# Display_driver.net
KiCad netlist of a schematic drawn in Altium Designer
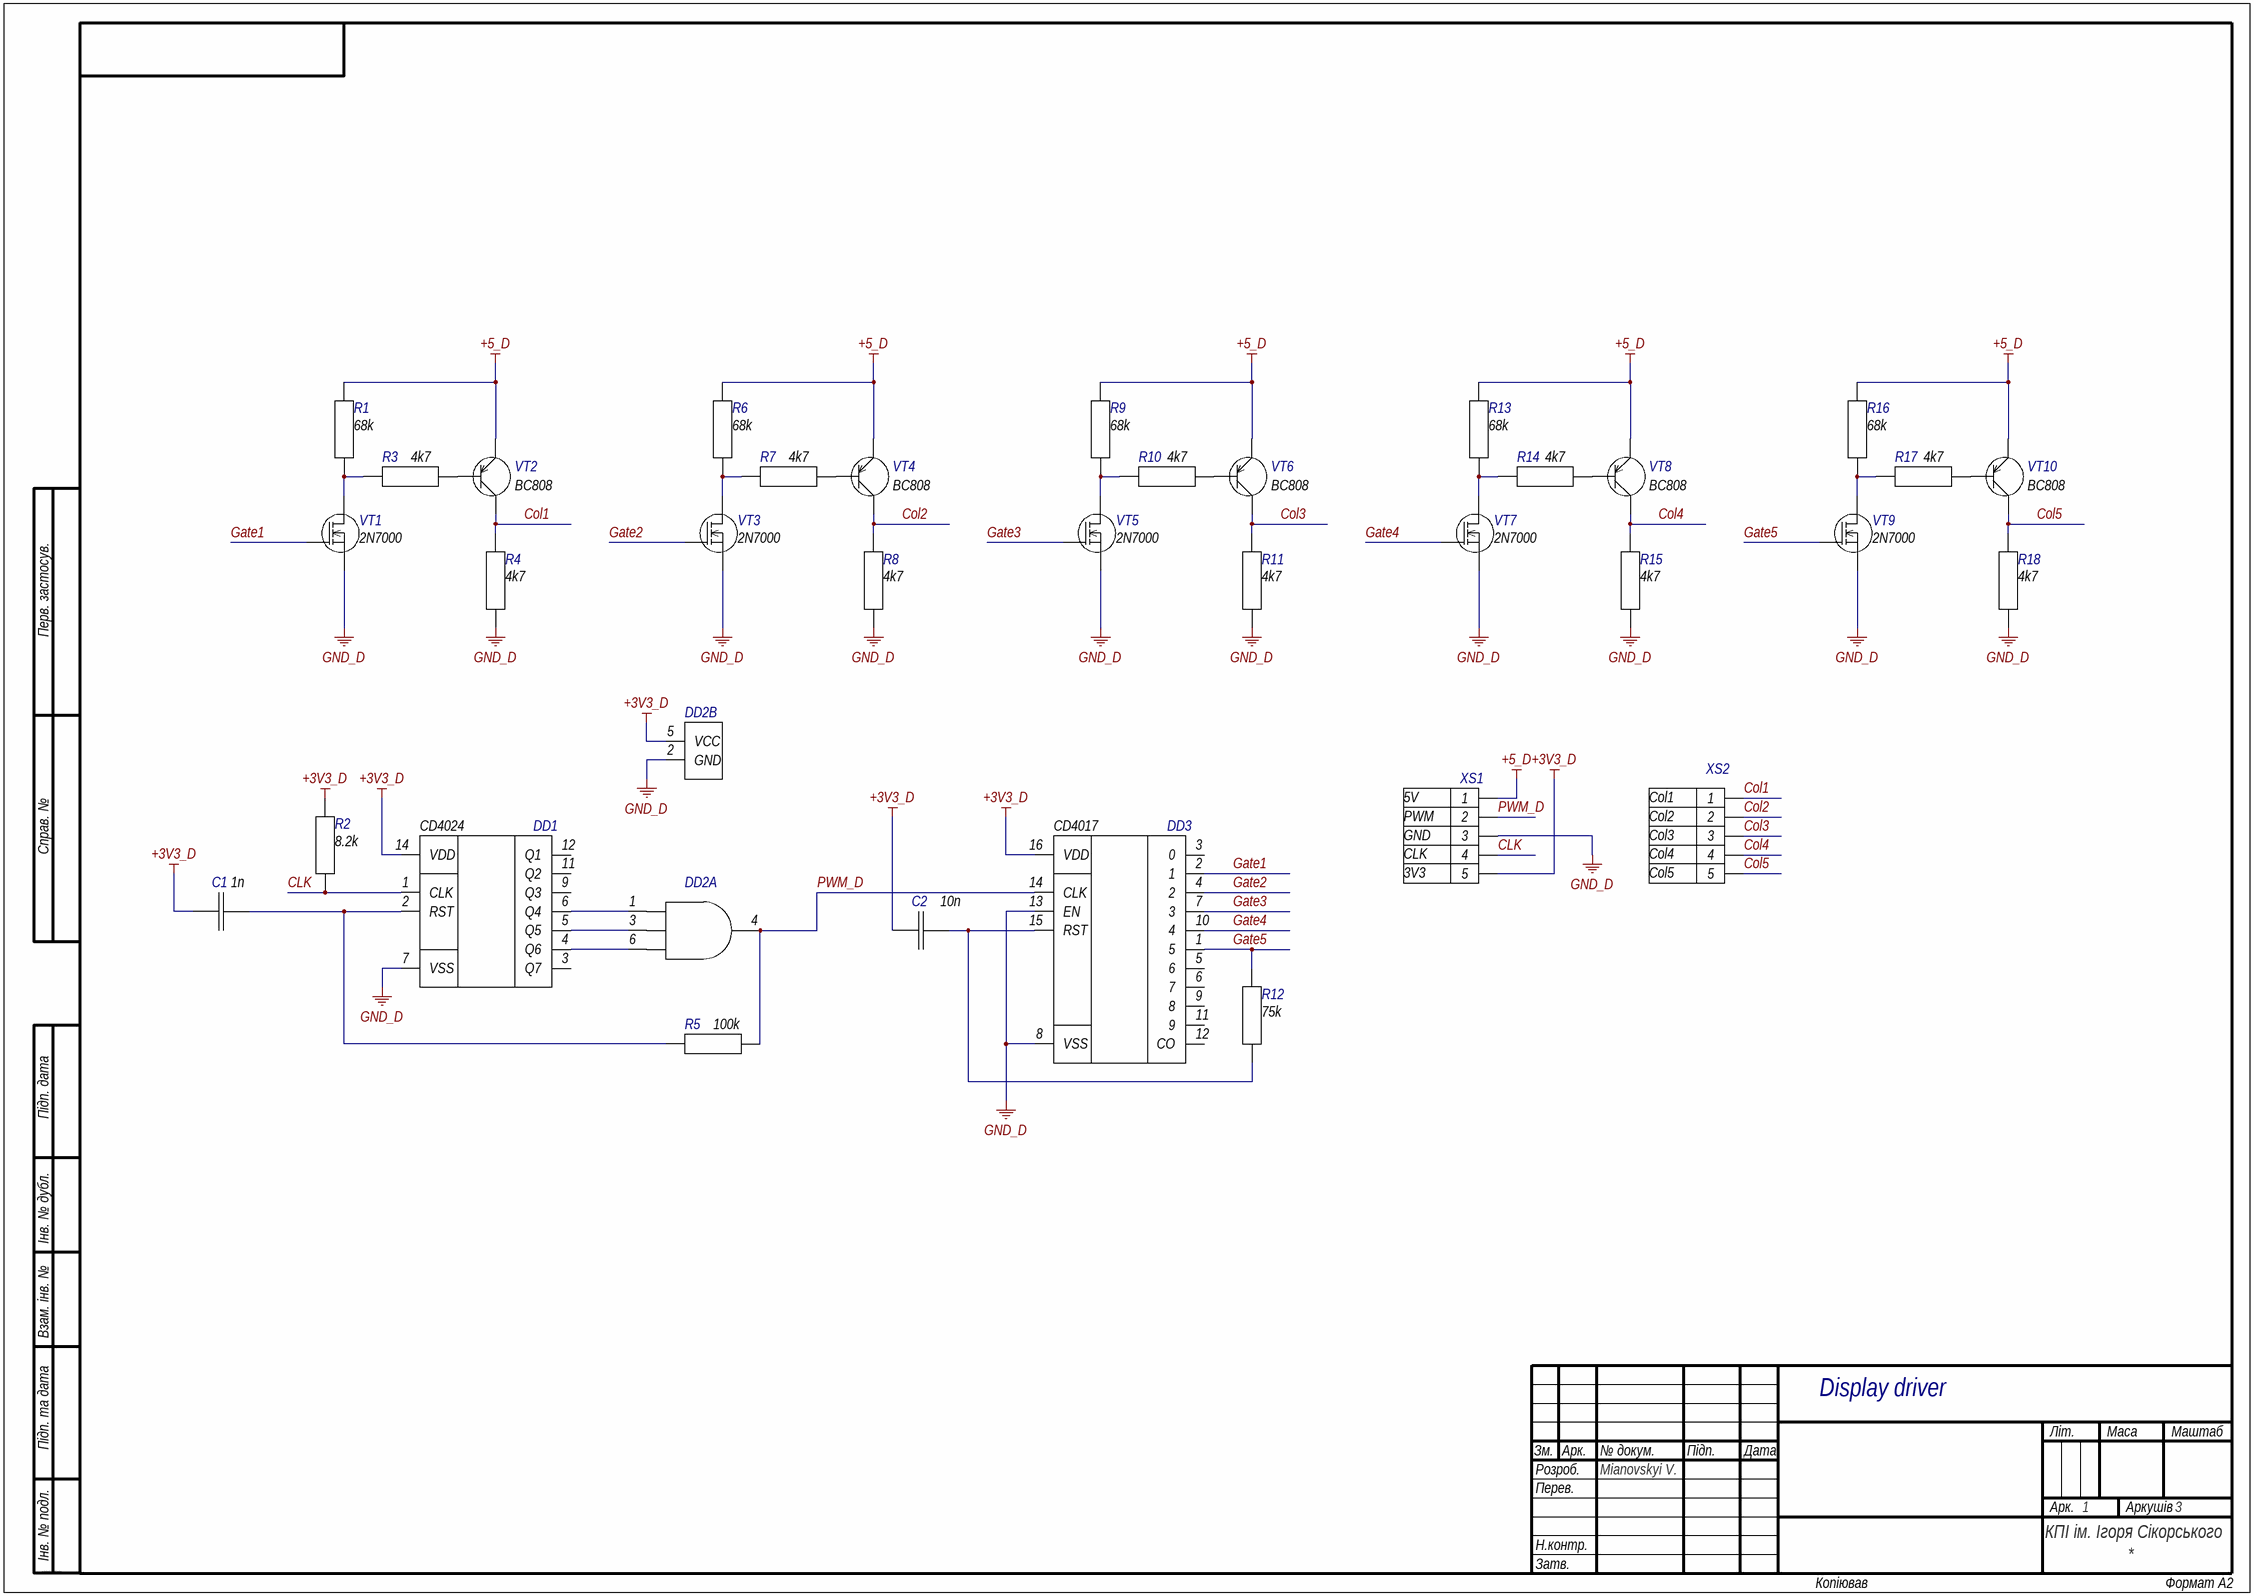
[diagram p0: Display_driver.SchDoc]

(export (version "E")
  (design (tool "Eeschema 10.0.6"))
  (components
    (comp (ref "C1")
      (value "1n")
      (footprint "CHIP-0805")
      (fields (field (name "Comment") "C0805"))
      (libsource (lib "Schlib1") (part "C0805"))
    )
    (comp (ref "C2")
      (value "10n")
      (footprint "CHIP-0402")
      (fields (field (name "Comment") "C0805"))
      (libsource (lib "Schlib1") (part "C0805"))
    )
    (comp (ref "DD1")
      (value "CD4024")
      (footprint "SOIC-14")
      (fields (field (name "NAME") "CD4024"))
      (libsource (lib "Schlib1") (part "CD4024"))
    )
    (comp (ref "DD2")
      (value "74LVC1G11")
      (footprint "SOT23-6")
      (libsource (lib "Schlib1") (part "74LVC1G11"))
    )
    (comp (ref "DD3")
      (value "CD4017")
      (footprint "SOIC-16")
      (fields (field (name "NAME") "CD4017"))
      (libsource (lib "Schlib1") (part "CD4017"))
    )
    (comp (ref "R1")
      (value "68k")
      (footprint "CHIP-0805")
      (fields (field (name "Comment") "R0805"))
      (libsource (lib "Schlib1") (part "R0805"))
    )
    (comp (ref "R2")
      (value "8.2k")
      (footprint "CHIP-0805")
      (fields (field (name "Comment") "R0805"))
      (libsource (lib "Schlib1") (part "R0805"))
    )
    (comp (ref "R3")
      (value "4k7")
      (footprint "CHIP-0402")
      (fields (field (name "Comment") "R0805"))
      (libsource (lib "") (part "R0805_1"))
    )
    (comp (ref "R4")
      (value "4k7")
      (footprint "CHIP-0402")
      (fields (field (name "Comment") "R0805"))
      (libsource (lib "Schlib1") (part "R0805"))
    )
    (comp (ref "R5")
      (value "100k")
      (footprint "CHIP-0805")
      (fields (field (name "Comment") "R0805"))
      (libsource (lib "") (part "R0805_1"))
    )
    (comp (ref "R6")
      (value "68k")
      (footprint "CHIP-0805")
      (fields (field (name "Comment") "R0805"))
      (libsource (lib "Schlib1") (part "R0805"))
    )
    (comp (ref "R7")
      (value "4k7")
      (footprint "CHIP-0402")
      (fields (field (name "Comment") "R0805"))
      (libsource (lib "") (part "R0805_1"))
    )
    (comp (ref "R8")
      (value "4k7")
      (footprint "CHIP-0402")
      (fields (field (name "Comment") "R0805"))
      (libsource (lib "Schlib1") (part "R0805"))
    )
    (comp (ref "R9")
      (value "68k")
      (footprint "CHIP-0805")
      (fields (field (name "Comment") "R0805"))
      (libsource (lib "Schlib1") (part "R0805"))
    )
    (comp (ref "R10")
      (value "4k7")
      (footprint "CHIP-0402")
      (fields (field (name "Comment") "R0805"))
      (libsource (lib "") (part "R0805_1"))
    )
    (comp (ref "R11")
      (value "4k7")
      (footprint "CHIP-0402")
      (fields (field (name "Comment") "R0805"))
      (libsource (lib "Schlib1") (part "R0805"))
    )
    (comp (ref "R12")
      (value "75k")
      (footprint "CHIP-0402")
      (fields (field (name "Comment") "R0805"))
      (libsource (lib "Schlib1") (part "R0805"))
    )
    (comp (ref "R13")
      (value "68k")
      (footprint "CHIP-0805")
      (fields (field (name "Comment") "R0805"))
      (libsource (lib "Schlib1") (part "R0805"))
    )
    (comp (ref "R14")
      (value "4k7")
      (footprint "CHIP-0402")
      (fields (field (name "Comment") "R0805"))
      (libsource (lib "") (part "R0805_1"))
    )
    (comp (ref "R15")
      (value "4k7")
      (footprint "CHIP-0402")
      (fields (field (name "Comment") "R0805"))
      (libsource (lib "Schlib1") (part "R0805"))
    )
    (comp (ref "R16")
      (value "68k")
      (footprint "CHIP-0805")
      (fields (field (name "Comment") "R0805"))
      (libsource (lib "Schlib1") (part "R0805"))
    )
    (comp (ref "R17")
      (value "4k7")
      (footprint "CHIP-0402")
      (fields (field (name "Comment") "R0805"))
      (libsource (lib "") (part "R0805_1"))
    )
    (comp (ref "R18")
      (value "4k7")
      (footprint "CHIP-0402")
      (fields (field (name "Comment") "R0805"))
      (libsource (lib "Schlib1") (part "R0805"))
    )
    (comp (ref "VT1")
      (value "2N7000")
      (footprint "SOT23-3")
      (fields (field (name "NAME") "2N7000"))
      (libsource (lib "Schlib1") (part "2N7000"))
    )
    (comp (ref "VT2")
      (value "BC808")
      (footprint "SOT23-3")
      (fields (field (name "NAME") "BC808"))
      (libsource (lib "Schlib1") (part "BC808"))
    )
    (comp (ref "VT3")
      (value "2N7000")
      (footprint "SOT23-3")
      (fields (field (name "NAME") "2N7000"))
      (libsource (lib "Schlib1") (part "2N7000"))
    )
    (comp (ref "VT4")
      (value "BC808")
      (footprint "SOT23-3")
      (fields (field (name "NAME") "BC808"))
      (libsource (lib "Schlib1") (part "BC808"))
    )
    (comp (ref "VT5")
      (value "2N7000")
      (footprint "SOT23-3")
      (fields (field (name "NAME") "2N7000"))
      (libsource (lib "Schlib1") (part "2N7000"))
    )
    (comp (ref "VT6")
      (value "BC808")
      (footprint "SOT23-3")
      (fields (field (name "NAME") "BC808"))
      (libsource (lib "Schlib1") (part "BC808"))
    )
    (comp (ref "VT7")
      (value "2N7000")
      (footprint "SOT23-3")
      (fields (field (name "NAME") "2N7000"))
      (libsource (lib "Schlib1") (part "2N7000"))
    )
    (comp (ref "VT8")
      (value "BC808")
      (footprint "SOT23-3")
      (fields (field (name "NAME") "BC808"))
      (libsource (lib "Schlib1") (part "BC808"))
    )
    (comp (ref "VT9")
      (value "2N7000")
      (footprint "SOT23-3")
      (fields (field (name "NAME") "2N7000"))
      (libsource (lib "Schlib1") (part "2N7000"))
    )
    (comp (ref "VT10")
      (value "BC808")
      (footprint "SOT23-3")
      (fields (field (name "NAME") "BC808"))
      (libsource (lib "Schlib1") (part "BC808"))
    )
    (comp (ref "XS1")
      (value "Socket")
      (footprint "SOCKET")
      (fields
        (field (name "PIN5") "3V3")
        (field (name "PIN4") "CLK")
        (field (name "PIN3") "GND")
        (field (name "PIN2") "PWM")
        (field (name "PIN1") "5V")
      )
      (libsource (lib "Schlib1") (part "Socket"))
    )
    (comp (ref "XS2")
      (value "Socket")
      (footprint "SOCKET")
      (fields
        (field (name "PIN5") "Col5")
        (field (name "PIN4") "Col4")
        (field (name "PIN3") "Col3")
        (field (name "PIN2") "Col2")
        (field (name "PIN1") "Col1")
      )
      (libsource (lib "Schlib1") (part "Socket"))
    )
  )
  (nets
    (net (code "1") (name "+3V3_D") (class "Default")
      (node (ref "C1") (pin "1") (pinfunction "1_1") (pintype "passive"))
      (node (ref "C2") (pin "1") (pinfunction "1_1") (pintype "passive"))
      (node (ref "DD1") (pin "14") (pinfunction "VDD_14") (pintype "passive"))
      (node (ref "DD2") (pin "5") (pinfunction "VCC_5") (pintype "passive"))
      (node (ref "DD3") (pin "16") (pinfunction "VDD_16") (pintype "passive"))
      (node (ref "R2") (pin "2") (pinfunction "2_2") (pintype "passive"))
      (node (ref "XS1") (pin "5") (pinfunction "5_5") (pintype "passive"))
    )
    (net (code "2") (name "+5_D") (class "Default")
      (node (ref "R1") (pin "2") (pinfunction "2_2") (pintype "passive"))
      (node (ref "R13") (pin "2") (pinfunction "2_2") (pintype "passive"))
      (node (ref "R16") (pin "2") (pinfunction "2_2") (pintype "passive"))
      (node (ref "R6") (pin "2") (pinfunction "2_2") (pintype "passive"))
      (node (ref "R9") (pin "2") (pinfunction "2_2") (pintype "passive"))
      (node (ref "VT10") (pin "2") (pinfunction "E_2") (pintype "passive"))
      (node (ref "VT2") (pin "2") (pinfunction "E_2") (pintype "passive"))
      (node (ref "VT4") (pin "2") (pinfunction "E_2") (pintype "passive"))
      (node (ref "VT6") (pin "2") (pinfunction "E_2") (pintype "passive"))
      (node (ref "VT8") (pin "2") (pinfunction "E_2") (pintype "passive"))
      (node (ref "XS1") (pin "1") (pinfunction "1_1") (pintype "passive"))
    )
    (net (code "3") (name "/CLK") (class "Default")
      (node (ref "DD1") (pin "1") (pinfunction "CLK_1") (pintype "passive"))
      (node (ref "R2") (pin "1") (pinfunction "1_1") (pintype "passive"))
      (node (ref "XS1") (pin "4") (pinfunction "4_4") (pintype "passive"))
    )
    (net (code "4") (name "/Col1") (class "Default")
      (node (ref "R4") (pin "2") (pinfunction "2_2") (pintype "passive"))
      (node (ref "VT2") (pin "3") (pinfunction "C_3") (pintype "passive"))
      (node (ref "XS2") (pin "1") (pinfunction "1_1") (pintype "passive"))
    )
    (net (code "5") (name "/Col2") (class "Default")
      (node (ref "R8") (pin "2") (pinfunction "2_2") (pintype "passive"))
      (node (ref "VT4") (pin "3") (pinfunction "C_3") (pintype "passive"))
      (node (ref "XS2") (pin "2") (pinfunction "2_2") (pintype "passive"))
    )
    (net (code "6") (name "/Col3") (class "Default")
      (node (ref "R11") (pin "2") (pinfunction "2_2") (pintype "passive"))
      (node (ref "VT6") (pin "3") (pinfunction "C_3") (pintype "passive"))
      (node (ref "XS2") (pin "3") (pinfunction "3_3") (pintype "passive"))
    )
    (net (code "7") (name "/Col4") (class "Default")
      (node (ref "R15") (pin "2") (pinfunction "2_2") (pintype "passive"))
      (node (ref "VT8") (pin "3") (pinfunction "C_3") (pintype "passive"))
      (node (ref "XS2") (pin "4") (pinfunction "4_4") (pintype "passive"))
    )
    (net (code "8") (name "/Col5") (class "Default")
      (node (ref "R18") (pin "2") (pinfunction "2_2") (pintype "passive"))
      (node (ref "VT10") (pin "3") (pinfunction "C_3") (pintype "passive"))
      (node (ref "XS2") (pin "5") (pinfunction "5_5") (pintype "passive"))
    )
    (net (code "9") (name "/Gate1") (class "Default")
      (node (ref "DD3") (pin "2") (pinfunction "1_2") (pintype "passive"))
      (node (ref "VT1") (pin "1") (pinfunction "G_1") (pintype "passive"))
    )
    (net (code "10") (name "/Gate2") (class "Default")
      (node (ref "DD3") (pin "4") (pinfunction "2_4") (pintype "passive"))
      (node (ref "VT3") (pin "1") (pinfunction "G_1") (pintype "passive"))
    )
    (net (code "11") (name "/Gate3") (class "Default")
      (node (ref "DD3") (pin "7") (pinfunction "3_7") (pintype "passive"))
      (node (ref "VT5") (pin "1") (pinfunction "G_1") (pintype "passive"))
    )
    (net (code "12") (name "/Gate4") (class "Default")
      (node (ref "DD3") (pin "10") (pinfunction "4_10") (pintype "passive"))
      (node (ref "VT7") (pin "1") (pinfunction "G_1") (pintype "passive"))
    )
    (net (code "13") (name "/Gate5") (class "Default")
      (node (ref "DD3") (pin "1") (pinfunction "5_1") (pintype "passive"))
      (node (ref "R12") (pin "2") (pinfunction "2_2") (pintype "passive"))
      (node (ref "VT9") (pin "1") (pinfunction "G_1") (pintype "passive"))
    )
    (net (code "14") (name "/PWM_D") (class "Default")
      (node (ref "DD2") (pin "4") (pinfunction "Y_4") (pintype "passive"))
      (node (ref "DD3") (pin "14") (pinfunction "CLK_14") (pintype "passive"))
      (node (ref "R5") (pin "2") (pinfunction "2_2") (pintype "passive"))
      (node (ref "XS1") (pin "2") (pinfunction "2_2") (pintype "passive"))
    )
    (net (code "15") (name "GND_D") (class "Default")
      (node (ref "DD1") (pin "7") (pinfunction "VSS_7") (pintype "passive"))
      (node (ref "DD2") (pin "2") (pinfunction "GND_2") (pintype "passive"))
      (node (ref "DD3") (pin "13") (pinfunction "EN_13") (pintype "passive"))
      (node (ref "DD3") (pin "8") (pinfunction "VSS_8") (pintype "passive"))
      (node (ref "R11") (pin "1") (pinfunction "1_1") (pintype "passive"))
      (node (ref "R15") (pin "1") (pinfunction "1_1") (pintype "passive"))
      (node (ref "R18") (pin "1") (pinfunction "1_1") (pintype "passive"))
      (node (ref "R4") (pin "1") (pinfunction "1_1") (pintype "passive"))
      (node (ref "R8") (pin "1") (pinfunction "1_1") (pintype "passive"))
      (node (ref "VT1") (pin "2") (pinfunction "S_2") (pintype "passive"))
      (node (ref "VT3") (pin "2") (pinfunction "S_2") (pintype "passive"))
      (node (ref "VT5") (pin "2") (pinfunction "S_2") (pintype "passive"))
      (node (ref "VT7") (pin "2") (pinfunction "S_2") (pintype "passive"))
      (node (ref "VT9") (pin "2") (pinfunction "S_2") (pintype "passive"))
      (node (ref "XS1") (pin "3") (pinfunction "3_3") (pintype "passive"))
    )
    (net (code "16") (name "Net-(DD1-Q4)") (class "Default")
      (node (ref "DD1") (pin "6") (pinfunction "Q4_6") (pintype "passive"))
      (node (ref "DD2") (pin "1") (pinfunction "A_1") (pintype "passive"))
    )
    (net (code "17") (name "Net-(DD1-Q5)") (class "Default")
      (node (ref "DD1") (pin "5") (pinfunction "Q5_5") (pintype "passive"))
      (node (ref "DD2") (pin "3") (pinfunction "B_3") (pintype "passive"))
    )
    (net (code "18") (name "Net-(DD1-Q6)") (class "Default")
      (node (ref "DD1") (pin "4") (pinfunction "Q6_4") (pintype "passive"))
      (node (ref "DD2") (pin "6") (pinfunction "C_6") (pintype "passive"))
    )
    (net (code "19") (name "Net-(DD1-RST)") (class "Default")
      (node (ref "C1") (pin "2") (pinfunction "2_2") (pintype "passive"))
      (node (ref "DD1") (pin "2") (pinfunction "RST_2") (pintype "passive"))
      (node (ref "R5") (pin "1") (pinfunction "1_1") (pintype "passive"))
    )
    (net (code "20") (name "Net-(DD3-RST)") (class "Default")
      (node (ref "C2") (pin "2") (pinfunction "2_2") (pintype "passive"))
      (node (ref "DD3") (pin "15") (pinfunction "RST_15") (pintype "passive"))
      (node (ref "R12") (pin "1") (pinfunction "1_1") (pintype "passive"))
    )
    (net (code "21") (name "Net-(VT1-D)") (class "Default")
      (node (ref "R1") (pin "1") (pinfunction "1_1") (pintype "passive"))
      (node (ref "R3") (pin "1") (pinfunction "1_1") (pintype "passive"))
      (node (ref "VT1") (pin "3") (pinfunction "D_3") (pintype "passive"))
    )
    (net (code "22") (name "Net-(VT2-B)") (class "Default")
      (node (ref "R3") (pin "2") (pinfunction "2_2") (pintype "passive"))
      (node (ref "VT2") (pin "1") (pinfunction "B_1") (pintype "passive"))
    )
    (net (code "23") (name "Net-(VT3-D)") (class "Default")
      (node (ref "R6") (pin "1") (pinfunction "1_1") (pintype "passive"))
      (node (ref "R7") (pin "1") (pinfunction "1_1") (pintype "passive"))
      (node (ref "VT3") (pin "3") (pinfunction "D_3") (pintype "passive"))
    )
    (net (code "24") (name "Net-(VT4-B)") (class "Default")
      (node (ref "R7") (pin "2") (pinfunction "2_2") (pintype "passive"))
      (node (ref "VT4") (pin "1") (pinfunction "B_1") (pintype "passive"))
    )
    (net (code "25") (name "Net-(VT5-D)") (class "Default")
      (node (ref "R10") (pin "1") (pinfunction "1_1") (pintype "passive"))
      (node (ref "R9") (pin "1") (pinfunction "1_1") (pintype "passive"))
      (node (ref "VT5") (pin "3") (pinfunction "D_3") (pintype "passive"))
    )
    (net (code "26") (name "Net-(VT6-B)") (class "Default")
      (node (ref "R10") (pin "2") (pinfunction "2_2") (pintype "passive"))
      (node (ref "VT6") (pin "1") (pinfunction "B_1") (pintype "passive"))
    )
    (net (code "27") (name "Net-(VT7-D)") (class "Default")
      (node (ref "R13") (pin "1") (pinfunction "1_1") (pintype "passive"))
      (node (ref "R14") (pin "1") (pinfunction "1_1") (pintype "passive"))
      (node (ref "VT7") (pin "3") (pinfunction "D_3") (pintype "passive"))
    )
    (net (code "28") (name "Net-(VT8-B)") (class "Default")
      (node (ref "R14") (pin "2") (pinfunction "2_2") (pintype "passive"))
      (node (ref "VT8") (pin "1") (pinfunction "B_1") (pintype "passive"))
    )
    (net (code "29") (name "Net-(VT9-D)") (class "Default")
      (node (ref "R16") (pin "1") (pinfunction "1_1") (pintype "passive"))
      (node (ref "R17") (pin "1") (pinfunction "1_1") (pintype "passive"))
      (node (ref "VT9") (pin "3") (pinfunction "D_3") (pintype "passive"))
    )
    (net (code "30") (name "Net-(VT10-B)") (class "Default")
      (node (ref "R17") (pin "2") (pinfunction "2_2") (pintype "passive"))
      (node (ref "VT10") (pin "1") (pinfunction "B_1") (pintype "passive"))
    )
    (net (code "31") (name "unconnected-(DD1-Q1-Pad12)") (class "Default")
      (node (ref "DD1") (pin "12") (pinfunction "Q1_12") (pintype "passive"))
    )
    (net (code "32") (name "unconnected-(DD1-Q2-Pad11)") (class "Default")
      (node (ref "DD1") (pin "11") (pinfunction "Q2_11") (pintype "passive"))
    )
    (net (code "33") (name "unconnected-(DD1-Q3-Pad9)") (class "Default")
      (node (ref "DD1") (pin "9") (pinfunction "Q3_9") (pintype "passive"))
    )
    (net (code "34") (name "unconnected-(DD1-Q7-Pad3)") (class "Default")
      (node (ref "DD1") (pin "3") (pinfunction "Q7_3") (pintype "passive"))
    )
    (net (code "35") (name "unconnected-(DD3-0-Pad3)") (class "Default")
      (node (ref "DD3") (pin "3") (pinfunction "0_3") (pintype "passive"))
    )
    (net (code "36") (name "unconnected-(DD3-6-Pad5)") (class "Default")
      (node (ref "DD3") (pin "5") (pinfunction "6_5") (pintype "passive"))
    )
    (net (code "37") (name "unconnected-(DD3-7-Pad6)") (class "Default")
      (node (ref "DD3") (pin "6") (pinfunction "7_6") (pintype "passive"))
    )
    (net (code "38") (name "unconnected-(DD3-8-Pad9)") (class "Default")
      (node (ref "DD3") (pin "9") (pinfunction "8_9") (pintype "passive"))
    )
    (net (code "39") (name "unconnected-(DD3-9-Pad11)") (class "Default")
      (node (ref "DD3") (pin "11") (pinfunction "9_11") (pintype "passive"))
    )
    (net (code "40") (name "unconnected-(DD3-CO-Pad12)") (class "Default")
      (node (ref "DD3") (pin "12") (pinfunction "CO_12") (pintype "passive"))
    )
  )
)
